# MPU.net
KiCad netlist of a schematic drawn in Altium Designer
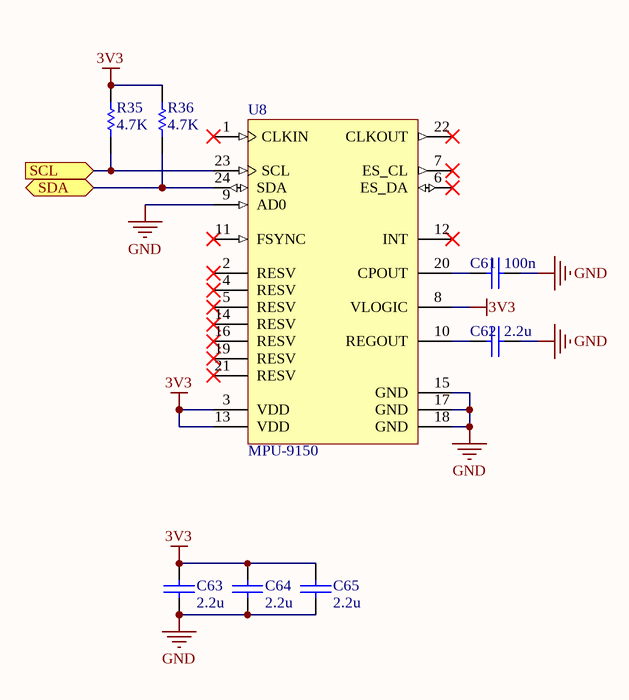
[diagram p0: MPU.SchDoc]

(export (version "E")
  (design (tool "Eeschema 10.0.6"))
  (components
    (comp (ref "C61")
      (value "100n")
      (footprint "0603C")
      (description "无极性电容")
      (libsource (lib "电容") (part "CAP"))
    )
    (comp (ref "C62")
      (value "2.2u")
      (footprint "0603C")
      (description "无极性电容")
      (libsource (lib "电容") (part "CAP"))
    )
    (comp (ref "C63")
      (value "2.2u")
      (footprint "0603C")
      (description "无极性电容")
      (libsource (lib "电容") (part "CAP"))
    )
    (comp (ref "C64")
      (value "2.2u")
      (footprint "0603C")
      (description "无极性电容")
      (libsource (lib "电容") (part "CAP"))
    )
    (comp (ref "C65")
      (value "2.2u")
      (footprint "0603C")
      (description "无极性电容")
      (libsource (lib "电容") (part "CAP"))
    )
    (comp (ref "R35") (value "4.7K") (footprint "0603R") (libsource (lib "电阻") (part "RES")))
    (comp (ref "R36") (value "4.7K") (footprint "0603R") (libsource (lib "电阻") (part "RES")))
    (comp (ref "U8")
      (value "MPU-9150")
      (footprint "IS-QFN-24_4000X4000X1100_V")
      (description "9-Axis MotionTracking Device, 2.375 to 3.465 V, -40 to 85 degC, 24-Pin QFN, RoHS, Tape and Reel")
      (fields (field (name "MANUFACTURER") "InvenSense"))
      (libsource (lib "Altium Content Vault") (part "IS-MPU-9150-QFN-24"))
    )
  )
  (nets
    (net (code "1") (name "/SCL") (class "Default")
      (node (ref "R35") (pin "1") (pinfunction "1_1") (pintype "passive"))
      (node (ref "U8") (pin "23") (pinfunction "SCL_23") (pintype "input"))
    )
    (net (code "2") (name "/SDA") (class "Default")
      (node (ref "R36") (pin "1") (pinfunction "1_1") (pintype "passive"))
      (node (ref "U8") (pin "24") (pinfunction "SDA_24") (pintype "bidirectional"))
    )
    (net (code "3") (name "3V3") (class "Default")
      (node (ref "C63") (pin "2") (pinfunction "2_2") (pintype "passive"))
      (node (ref "C64") (pin "2") (pinfunction "2_2") (pintype "passive"))
      (node (ref "C65") (pin "2") (pinfunction "2_2") (pintype "passive"))
      (node (ref "R35") (pin "2") (pinfunction "2_2") (pintype "passive"))
      (node (ref "R36") (pin "2") (pinfunction "2_2") (pintype "passive"))
      (node (ref "U8") (pin "13") (pinfunction "VDD_13") (pintype "power_in"))
      (node (ref "U8") (pin "3") (pinfunction "VDD_3") (pintype "power_in"))
      (node (ref "U8") (pin "8") (pinfunction "VLOGIC_8") (pintype "power_in"))
    )
    (net (code "4") (name "GND") (class "Default")
      (node (ref "C61") (pin "2") (pinfunction "2_2") (pintype "passive"))
      (node (ref "C62") (pin "2") (pinfunction "2_2") (pintype "passive"))
      (node (ref "C63") (pin "1") (pinfunction "1_1") (pintype "passive"))
      (node (ref "C64") (pin "1") (pinfunction "1_1") (pintype "passive"))
      (node (ref "C65") (pin "1") (pinfunction "1_1") (pintype "passive"))
      (node (ref "U8") (pin "15") (pinfunction "GND_15") (pintype "power_in"))
      (node (ref "U8") (pin "17") (pinfunction "GND_17") (pintype "power_in"))
      (node (ref "U8") (pin "18") (pinfunction "GND_18") (pintype "power_in"))
      (node (ref "U8") (pin "9") (pinfunction "AD0_9") (pintype "input"))
    )
    (net (code "5") (name "Net-(U8-CPOUT)") (class "Default")
      (node (ref "C61") (pin "1") (pinfunction "1_1") (pintype "passive"))
      (node (ref "U8") (pin "20") (pinfunction "CPOUT_20") (pintype "passive"))
    )
    (net (code "6") (name "Net-(U8-REGOUT)") (class "Default")
      (node (ref "C62") (pin "1") (pinfunction "1_1") (pintype "passive"))
      (node (ref "U8") (pin "10") (pinfunction "REGOUT_10") (pintype "passive"))
    )
    (net (code "7") (name "unconnected-(U8-CLKIN-Pad1)") (class "Default")
      (node (ref "U8") (pin "1") (pinfunction "CLKIN_1") (pintype "input+no_connect"))
    )
    (net (code "8") (name "unconnected-(U8-CLKOUT-Pad22)") (class "Default")
      (node (ref "U8") (pin "22") (pinfunction "CLKOUT_22") (pintype "output+no_connect"))
    )
    (net (code "9") (name "unconnected-(U8-ES_CL-Pad7)") (class "Default")
      (node (ref "U8") (pin "7") (pinfunction "ES_CL_7") (pintype "output+no_connect"))
    )
    (net (code "10") (name "unconnected-(U8-ES_DA-Pad6)") (class "Default")
      (node (ref "U8") (pin "6") (pinfunction "ES_DA_6") (pintype "bidirectional+no_connect"))
    )
    (net (code "11") (name "unconnected-(U8-FSYNC-Pad11)") (class "Default")
      (node (ref "U8") (pin "11") (pinfunction "FSYNC_11") (pintype "input+no_connect"))
    )
    (net (code "12") (name "unconnected-(U8-INT-Pad12)") (class "Default")
      (node (ref "U8") (pin "12") (pinfunction "INT_12") (pintype "open_collector+no_connect"))
    )
    (net (code "13") (name "unconnected-(U8-RESV-Pad2)") (class "Default")
      (node (ref "U8") (pin "2") (pinfunction "RESV_2") (pintype "passive+no_connect"))
    )
    (net (code "14") (name "unconnected-(U8-RESV-Pad4)") (class "Default")
      (node (ref "U8") (pin "4") (pinfunction "RESV_4") (pintype "passive+no_connect"))
    )
    (net (code "15") (name "unconnected-(U8-RESV-Pad5)") (class "Default")
      (node (ref "U8") (pin "5") (pinfunction "RESV_5") (pintype "passive+no_connect"))
    )
    (net (code "16") (name "unconnected-(U8-RESV-Pad14)") (class "Default")
      (node (ref "U8") (pin "14") (pinfunction "RESV_14") (pintype "passive+no_connect"))
    )
    (net (code "17") (name "unconnected-(U8-RESV-Pad16)") (class "Default")
      (node (ref "U8") (pin "16") (pinfunction "RESV_16") (pintype "passive+no_connect"))
    )
    (net (code "18") (name "unconnected-(U8-RESV-Pad19)") (class "Default")
      (node (ref "U8") (pin "19") (pinfunction "RESV_19") (pintype "passive+no_connect"))
    )
    (net (code "19") (name "unconnected-(U8-RESV-Pad21)") (class "Default")
      (node (ref "U8") (pin "21") (pinfunction "RESV_21") (pintype "passive+no_connect"))
    )
  )
)
